# Schem_V1.net
KiCad netlist of a schematic drawn in Altium Designer
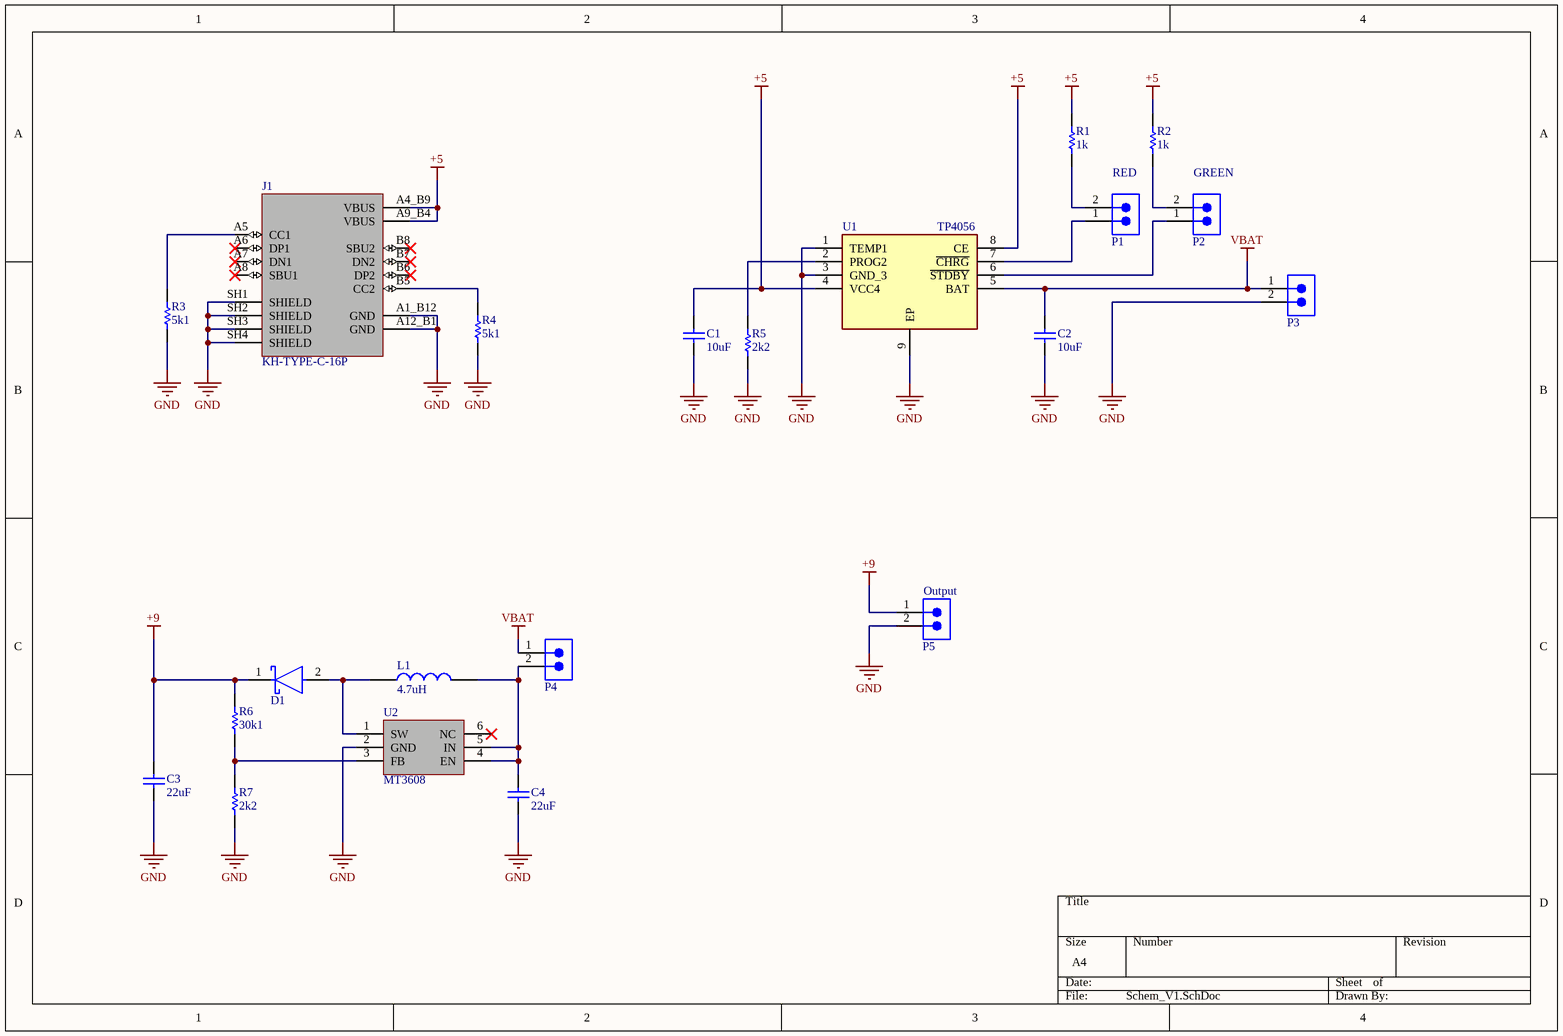
[diagram p0: Schem_V1.SchDoc]

(export (version "E")
  (design (tool "Eeschema 10.0.6"))
  (components
    (comp (ref "C1")
      (value "10uF")
      (footprint "Wurth 0603 capacitor")
      (fields (field (name "Comment") "Generic Capacitor 10uF 0603"))
      (libsource (lib "Passives") (part "Generic Capacitor 10uF 0603"))
    )
    (comp (ref "C2")
      (value "10uF")
      (footprint "Wurth 0603 capacitor")
      (fields (field (name "Comment") "Generic Capacitor 10uF 0603"))
      (libsource (lib "Passives") (part "Generic Capacitor 10uF 0603"))
    )
    (comp (ref "C3")
      (value "22uF")
      (footprint "Wurth 0805 capacitor")
      (fields (field (name "Comment") "Generic Capacitor 22uF 0805"))
      (libsource (lib "Passives") (part "Generic Capacitor 22uF 0805"))
    )
    (comp (ref "C4")
      (value "22uF")
      (footprint "Wurth 0805 capacitor")
      (fields (field (name "Comment") "Generic Capacitor 22uF 0805"))
      (libsource (lib "Passives") (part "Generic Capacitor 22uF 0805"))
    )
    (comp (ref "D1")
      (value "V1FM10-M3/H")
      (footprint "FP-V1FM10-M3-H-MFG")
      (description "1A 100V SMF TRENCH SKY RECT")
      (libsource (lib "Altium Content Vault") (part "1d6ec82d83fb6aee721767c19dac4b9"))
    )
    (comp (ref "J1")
      (value "KH-TYPE-C-16P")
      (footprint "KINGHELM_KH-TYPE-C-16P")
      (fields (field (name "MF") "kinghelm"))
      (libsource (lib "Connectors") (part "Kinghelm KH-TYPE-C-16P"))
    )
    (comp (ref "L1")
      (value "4.7uH")
      (footprint "cjiang FTC252010S4R7MBCA")
      (description "cjiang FTC252010S4R7MBCA")
      (fields (field (name "Comment") "FTC252010S4R7MBCA"))
      (libsource (lib "Passives") (part "2010 4.7µH  2A"))
    )
    (comp (ref "P1")
      (value "61300211121")
      (footprint "2x1 2.54mm M")
      (description "WR-PHD Pin Header, THT, Vertical, pitch 2.54mm, 1 Row, 2P")
      (fields (field (name "MANUFACTURER") "Wurth Elektronik"))
      (libsource (lib "2.54mm_pin_headers") (part "2P"))
    )
    (comp (ref "P2")
      (value "61300211121")
      (footprint "2x1 2.54mm M")
      (description "WR-PHD Pin Header, THT, Vertical, pitch 2.54mm, 1 Row, 2P")
      (fields (field (name "MANUFACTURER") "Wurth Elektronik"))
      (libsource (lib "2.54mm_pin_headers") (part "2P"))
    )
    (comp (ref "P3")
      (value "61300211121")
      (footprint "2x1 2.54mm M")
      (description "WR-PHD Pin Header, THT, Vertical, pitch 2.54mm, 1 Row, 2P")
      (fields (field (name "MANUFACTURER") "Wurth Elektronik"))
      (libsource (lib "2.54mm_pin_headers") (part "2P"))
    )
    (comp (ref "P4")
      (value "61300211121")
      (footprint "2x1 2.54mm M")
      (description "WR-PHD Pin Header, THT, Vertical, pitch 2.54mm, 1 Row, 2P")
      (fields (field (name "MANUFACTURER") "Wurth Elektronik"))
      (libsource (lib "2.54mm_pin_headers") (part "2P"))
    )
    (comp (ref "P5")
      (value "61300211121")
      (footprint "2x1 2.54mm F")
      (description "WR-PHD Pin Header, THT, Vertical, pitch 2.54mm, 1 Row, 2P")
      (fields (field (name "MANUFACTURER") "Wurth Elektronik"))
      (libsource (lib "2.54mm_pin_headers") (part "2P"))
    )
    (comp (ref "R1")
      (value "1k")
      (footprint "Wurth 0603 Resistor")
      (fields (field (name "Comment") "Generic Resistor 1k 0603"))
      (libsource (lib "Passives") (part "Generic Resistor 1k 0603"))
    )
    (comp (ref "R2")
      (value "1k")
      (footprint "Wurth 0603 Resistor")
      (fields (field (name "Comment") "Generic Resistor 1k 0603"))
      (libsource (lib "Passives") (part "Generic Resistor 1k 0603"))
    )
    (comp (ref "R3")
      (value "5k1")
      (footprint "0805 Resistor")
      (fields (field (name "Comment") "Generic Resistor 5k1 0805"))
      (libsource (lib "Passives") (part "Generic Resistor 5k1 0805"))
    )
    (comp (ref "R4")
      (value "5k1")
      (footprint "0805 Resistor")
      (fields (field (name "Comment") "Generic Resistor 5k1 0805"))
      (libsource (lib "Passives") (part "Generic Resistor 5k1 0805"))
    )
    (comp (ref "R5")
      (value "2k2")
      (footprint "Wurth 0603 Resistor")
      (fields (field (name "Comment") "Generic Resistor 2k2 0603"))
      (libsource (lib "Passives") (part "Generic Resistor 2k2 0603"))
    )
    (comp (ref "R6")
      (value "30k1")
      (footprint "Wurth 0603 Resistor")
      (fields (field (name "Comment") "Generic Resistor 30k1 0603"))
      (libsource (lib "Passives") (part "Generic Resistor 30k1 0603"))
    )
    (comp (ref "R7")
      (value "2k2")
      (footprint "Wurth 0603 Resistor")
      (fields (field (name "Comment") "Generic Resistor 2k2 0603"))
      (libsource (lib "Passives") (part "Generic Resistor 2k2 0603"))
    )
    (comp (ref "U1")
      (value "TP4056")
      (footprint "SamacSys:SOIC127P600X175-9N")
      (description "Lipo charger")
      (libsource (lib "*") (part "TP4056"))
    )
    (comp (ref "U2")
      (value "MT3608")
      (footprint "Aerosemi SOT23-6")
      (description "Integrated Circuit")
      (libsource (lib "Boost_Converter") (part "Aerosemi MT3608"))
    )
  )
  (nets
    (net (code "1") (name "+5") (class "Default")
      (node (ref "C1") (pin "2") (pinfunction "2_2") (pintype "passive"))
      (node (ref "J1") (pin "A4_B9") (pinfunction "VBUS_A4_B9") (pintype "power_in"))
      (node (ref "J1") (pin "A9_B4") (pinfunction "VBUS_A9_B4") (pintype "power_in"))
      (node (ref "R1") (pin "2") (pinfunction "2_2") (pintype "passive"))
      (node (ref "R2") (pin "2") (pinfunction "2_2") (pintype "passive"))
      (node (ref "U1") (pin "4") (pinfunction "VCC4_4") (pintype "passive"))
      (node (ref "U1") (pin "8") (pinfunction "CE_8") (pintype "passive"))
    )
    (net (code "2") (name "+9") (class "Default")
      (node (ref "C3") (pin "2") (pinfunction "2_2") (pintype "passive"))
      (node (ref "D1") (pin "1") (pinfunction "C_1") (pintype "passive"))
      (node (ref "P5") (pin "1") (pinfunction "1_1") (pintype "passive"))
      (node (ref "R6") (pin "2") (pinfunction "2_2") (pintype "passive"))
    )
    (net (code "3") (name "GND") (class "Default")
      (node (ref "C1") (pin "1") (pinfunction "1_1") (pintype "passive"))
      (node (ref "C2") (pin "1") (pinfunction "1_1") (pintype "passive"))
      (node (ref "C3") (pin "1") (pinfunction "1_1") (pintype "passive"))
      (node (ref "C4") (pin "1") (pinfunction "1_1") (pintype "passive"))
      (node (ref "J1") (pin "A12_B1") (pinfunction "GND_A12_B1") (pintype "power_in"))
      (node (ref "J1") (pin "A1_B12") (pinfunction "GND_A1_B12") (pintype "power_in"))
      (node (ref "J1") (pin "SH1") (pinfunction "SHIELD_SH1") (pintype "passive"))
      (node (ref "J1") (pin "SH2") (pinfunction "SHIELD_SH2") (pintype "passive"))
      (node (ref "J1") (pin "SH3") (pinfunction "SHIELD_SH3") (pintype "passive"))
      (node (ref "J1") (pin "SH4") (pinfunction "SHIELD_SH4") (pintype "passive"))
      (node (ref "P3") (pin "2") (pinfunction "2_2") (pintype "passive"))
      (node (ref "P5") (pin "2") (pinfunction "2_2") (pintype "passive"))
      (node (ref "R3") (pin "1") (pinfunction "1_1") (pintype "passive"))
      (node (ref "R4") (pin "1") (pinfunction "1_1") (pintype "passive"))
      (node (ref "R5") (pin "1") (pinfunction "1_1") (pintype "passive"))
      (node (ref "R7") (pin "1") (pinfunction "1_1") (pintype "passive"))
      (node (ref "U1") (pin "1") (pinfunction "TEMP1_1") (pintype "passive"))
      (node (ref "U1") (pin "3") (pinfunction "GND_3_3") (pintype "passive"))
      (node (ref "U1") (pin "9") (pinfunction "EP_9") (pintype "passive"))
      (node (ref "U2") (pin "2") (pinfunction "GND_2") (pintype "passive"))
    )
    (net (code "4") (name "Net-(D1-A)") (class "Default")
      (node (ref "D1") (pin "2") (pinfunction "A_2") (pintype "passive"))
      (node (ref "L1") (pin "1") (pinfunction "1_1") (pintype "passive"))
      (node (ref "U2") (pin "1") (pinfunction "SW_1") (pintype "passive"))
    )
    (net (code "5") (name "Net-(J1-CC1)") (class "Default")
      (node (ref "J1") (pin "A5") (pinfunction "CC1_A5") (pintype "bidirectional"))
      (node (ref "R3") (pin "2") (pinfunction "2_2") (pintype "passive"))
    )
    (net (code "6") (name "Net-(J1-CC2)") (class "Default")
      (node (ref "J1") (pin "B5") (pinfunction "CC2_B5") (pintype "bidirectional"))
      (node (ref "R4") (pin "2") (pinfunction "2_2") (pintype "passive"))
    )
    (net (code "7") (name "Net-(P1-Pad2)") (class "Default")
      (node (ref "P1") (pin "2") (pinfunction "2_2") (pintype "passive"))
      (node (ref "R1") (pin "1") (pinfunction "1_1") (pintype "passive"))
    )
    (net (code "8") (name "Net-(P2-Pad2)") (class "Default")
      (node (ref "P2") (pin "2") (pinfunction "2_2") (pintype "passive"))
      (node (ref "R2") (pin "1") (pinfunction "1_1") (pintype "passive"))
    )
    (net (code "9") (name "Net-(U1-PROG2)") (class "Default")
      (node (ref "R5") (pin "2") (pinfunction "2_2") (pintype "passive"))
      (node (ref "U1") (pin "2") (pinfunction "PROG2_2") (pintype "passive"))
    )
    (net (code "10") (name "Net-(U1-~{CHRG})") (class "Default")
      (node (ref "P1") (pin "1") (pinfunction "1_1") (pintype "passive"))
      (node (ref "U1") (pin "7") (pinfunction "~{CHRG}_7") (pintype "passive"))
    )
    (net (code "11") (name "Net-(U1-~{STDBY})") (class "Default")
      (node (ref "P2") (pin "1") (pinfunction "1_1") (pintype "passive"))
      (node (ref "U1") (pin "6") (pinfunction "~{STDBY}_6") (pintype "passive"))
    )
    (net (code "12") (name "Net-(U2-EN)") (class "Default")
      (node (ref "C4") (pin "2") (pinfunction "2_2") (pintype "passive"))
      (node (ref "L1") (pin "2") (pinfunction "2_2") (pintype "passive"))
      (node (ref "P4") (pin "2") (pinfunction "2_2") (pintype "passive"))
      (node (ref "U2") (pin "4") (pinfunction "EN_4") (pintype "passive"))
      (node (ref "U2") (pin "5") (pinfunction "IN_5") (pintype "passive"))
    )
    (net (code "13") (name "Net-(U2-FB)") (class "Default")
      (node (ref "R6") (pin "1") (pinfunction "1_1") (pintype "passive"))
      (node (ref "R7") (pin "2") (pinfunction "2_2") (pintype "passive"))
      (node (ref "U2") (pin "3") (pinfunction "FB_3") (pintype "passive"))
    )
    (net (code "14") (name "VBAT") (class "Default")
      (node (ref "C2") (pin "2") (pinfunction "2_2") (pintype "passive"))
      (node (ref "P3") (pin "1") (pinfunction "1_1") (pintype "passive"))
      (node (ref "P4") (pin "1") (pinfunction "1_1") (pintype "passive"))
      (node (ref "U1") (pin "5") (pinfunction "BAT_5") (pintype "passive"))
    )
    (net (code "15") (name "unconnected-(J1-DN1-PadA7)") (class "Default")
      (node (ref "J1") (pin "A7") (pinfunction "DN1_A7") (pintype "bidirectional+no_connect"))
    )
    (net (code "16") (name "unconnected-(J1-DN2-PadB7)") (class "Default")
      (node (ref "J1") (pin "B7") (pinfunction "DN2_B7") (pintype "bidirectional+no_connect"))
    )
    (net (code "17") (name "unconnected-(J1-DP1-PadA6)") (class "Default")
      (node (ref "J1") (pin "A6") (pinfunction "DP1_A6") (pintype "bidirectional+no_connect"))
    )
    (net (code "18") (name "unconnected-(J1-DP2-PadB6)") (class "Default")
      (node (ref "J1") (pin "B6") (pinfunction "DP2_B6") (pintype "bidirectional+no_connect"))
    )
    (net (code "19") (name "unconnected-(J1-SBU1-PadA8)") (class "Default")
      (node (ref "J1") (pin "A8") (pinfunction "SBU1_A8") (pintype "bidirectional+no_connect"))
    )
    (net (code "20") (name "unconnected-(J1-SBU2-PadB8)") (class "Default")
      (node (ref "J1") (pin "B8") (pinfunction "SBU2_B8") (pintype "bidirectional+no_connect"))
    )
    (net (code "21") (name "unconnected-(U2-NC-Pad6)") (class "Default")
      (node (ref "U2") (pin "6") (pinfunction "NC_6") (pintype "passive+no_connect"))
    )
  )
)
